# water-sensor.net
KiCad netlist of a schematic drawn in EAGLE
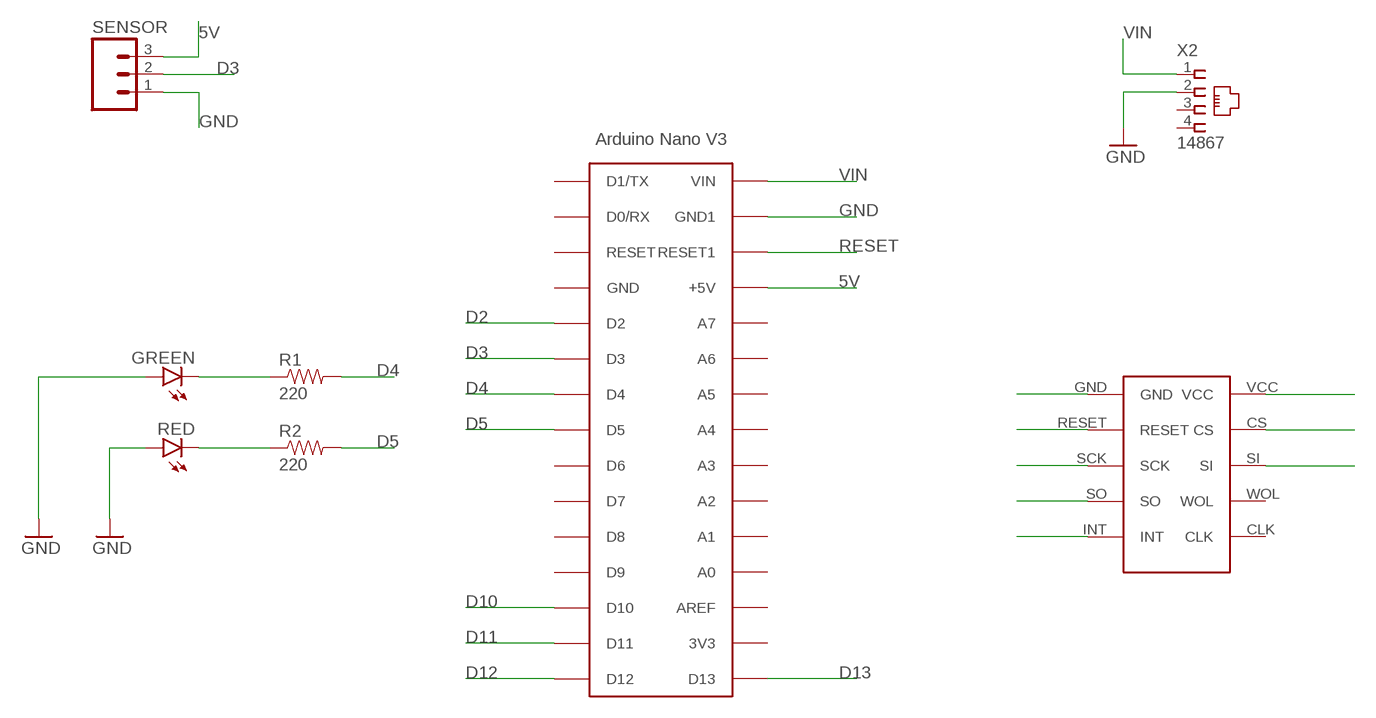
[diagram p0: schematic, sheet 1]

(export (version "E")
  (design (tool "Eeschema 10.0.6"))
  (components
    (comp (ref "GREEN")
      (value "LED3MM")
      (footprint "eagle-import:LED3MM")
      (libsource (lib "eagle-import") (part "LED3MM"))
    )
    (comp (ref "R1")
      (value "220")
      (footprint "eagle-import:AXIAL-0.5")
      (libsource (lib "eagle-import") (part "RESISTORPTH-1/2W"))
    )
    (comp (ref "R2")
      (value "220")
      (footprint "eagle-import:AXIAL-0.5")
      (libsource (lib "eagle-import") (part "RESISTORPTH-1/2W"))
    )
    (comp (ref "RED")
      (value "LED3MM")
      (footprint "eagle-import:LED3MM")
      (libsource (lib "eagle-import") (part "LED3MM"))
    )
    (comp (ref "SENSOR")
      (value "M03LONGPADS")
      (footprint "eagle-import:1X03_LONGPADS")
      (libsource (lib "eagle-import") (part "M03LONGPADS"))
    )
    (comp (ref "U$1")
      (value "ARDUINONANO")
      (footprint "eagle-import:PDIP-32")
      (libsource (lib "eagle-import") (part "ARDUINONANO"))
    )
    (comp (ref "U$2")
      (value "ENC28J60ENC28J60")
      (footprint "eagle-import:ENC28J60")
      (libsource (lib "eagle-import") (part "ENC28J60ENC28J60"))
    )
    (comp (ref "X2")
      (value "14867")
      (footprint "eagle-import:14867")
      (libsource (lib "eagle-import") (part "14867"))
    )
  )
  (nets
    (net (code "1") (name "/5V") (class "Default")
      (node (ref "SENSOR") (pin "3") (pinfunction "3_3") (pintype "passive"))
      (node (ref "U$1") (pin "+5V") (pinfunction "+5V_+5V") (pintype "bidirectional"))
      (node (ref "U$2") (pin "VCC") (pinfunction "VCC_VCC") (pintype "bidirectional"))
    )
    (net (code "2") (name "/D2") (class "Default")
      (node (ref "U$1") (pin "D2") (pinfunction "D2_D2") (pintype "bidirectional"))
      (node (ref "U$2") (pin "INT") (pinfunction "INT_INT") (pintype "bidirectional"))
    )
    (net (code "3") (name "/D3") (class "Default")
      (node (ref "SENSOR") (pin "2") (pinfunction "2_2") (pintype "passive"))
      (node (ref "U$1") (pin "D3") (pinfunction "D3_D3") (pintype "bidirectional"))
    )
    (net (code "4") (name "/D4") (class "Default")
      (node (ref "R1") (pin "P$2") (pinfunction "2_P$2") (pintype "passive"))
      (node (ref "U$1") (pin "D4") (pinfunction "D4_D4") (pintype "bidirectional"))
    )
    (net (code "5") (name "/D5") (class "Default")
      (node (ref "R2") (pin "P$2") (pinfunction "2_P$2") (pintype "passive"))
      (node (ref "U$1") (pin "D5") (pinfunction "D5_D5") (pintype "bidirectional"))
    )
    (net (code "6") (name "/D10") (class "Default")
      (node (ref "U$1") (pin "D10") (pinfunction "D10_D10") (pintype "bidirectional"))
      (node (ref "U$2") (pin "CS") (pinfunction "CS_CS") (pintype "bidirectional"))
    )
    (net (code "7") (name "/D11") (class "Default")
      (node (ref "U$1") (pin "D11") (pinfunction "D11_D11") (pintype "bidirectional"))
      (node (ref "U$2") (pin "SI") (pinfunction "SI_SI") (pintype "bidirectional"))
    )
    (net (code "8") (name "/D12") (class "Default")
      (node (ref "U$1") (pin "D12") (pinfunction "D12_D12") (pintype "bidirectional"))
      (node (ref "U$2") (pin "SO") (pinfunction "SO_SO") (pintype "bidirectional"))
    )
    (net (code "9") (name "/D13") (class "Default")
      (node (ref "U$1") (pin "D13") (pinfunction "D13_D13") (pintype "bidirectional"))
      (node (ref "U$2") (pin "SCK") (pinfunction "SCK_SCK") (pintype "bidirectional"))
    )
    (net (code "10") (name "/RESET") (class "Default")
      (node (ref "U$1") (pin "RESET1") (pinfunction "RESET1_RESET1") (pintype "bidirectional"))
      (node (ref "U$2") (pin "RESET") (pinfunction "RESET_RESET") (pintype "bidirectional"))
    )
    (net (code "11") (name "/VIN") (class "Default")
      (node (ref "U$1") (pin "VIN") (pinfunction "VIN_VIN") (pintype "bidirectional"))
      (node (ref "X2") (pin "1") (pinfunction "1_1") (pintype "passive"))
    )
    (net (code "12") (name "GND") (class "Default")
      (node (ref "GREEN") (pin "A") (pinfunction "A_A") (pintype "passive"))
      (node (ref "RED") (pin "A") (pinfunction "A_A") (pintype "passive"))
      (node (ref "SENSOR") (pin "1") (pinfunction "1_1") (pintype "passive"))
      (node (ref "U$1") (pin "GND1") (pinfunction "GND1_GND1") (pintype "bidirectional"))
      (node (ref "U$2") (pin "GND") (pinfunction "GND_GND") (pintype "bidirectional"))
      (node (ref "X2") (pin "2") (pinfunction "2_2") (pintype "passive"))
    )
    (net (code "13") (name "Net-(GREEN-C)") (class "Default")
      (node (ref "GREEN") (pin "K") (pinfunction "C_K") (pintype "passive"))
      (node (ref "R1") (pin "P$1") (pinfunction "1_P$1") (pintype "passive"))
    )
    (net (code "14") (name "Net-(R2-1)") (class "Default")
      (node (ref "R2") (pin "P$1") (pinfunction "1_P$1") (pintype "passive"))
      (node (ref "RED") (pin "K") (pinfunction "C_K") (pintype "passive"))
    )
    (net (code "15") (name "unconnected-(U$1-A0-PadA7)") (class "Default")
      (node (ref "U$1") (pin "A7") (pinfunction "A0_A7") (pintype "bidirectional"))
    )
    (net (code "16") (name "unconnected-(U$1-A1-PadA6)") (class "Default")
      (node (ref "U$1") (pin "A6") (pinfunction "A1_A6") (pintype "bidirectional"))
    )
    (net (code "17") (name "unconnected-(U$1-A2-PadA5)") (class "Default")
      (node (ref "U$1") (pin "A5") (pinfunction "A2_A5") (pintype "bidirectional"))
    )
    (net (code "18") (name "unconnected-(U$1-A3-PadA4)") (class "Default")
      (node (ref "U$1") (pin "A4") (pinfunction "A3_A4") (pintype "bidirectional"))
    )
    (net (code "19") (name "unconnected-(U$1-A4-PadA3)") (class "Default")
      (node (ref "U$1") (pin "A3") (pinfunction "A4_A3") (pintype "bidirectional"))
    )
    (net (code "20") (name "unconnected-(U$1-A5-PadA2)") (class "Default")
      (node (ref "U$1") (pin "A2") (pinfunction "A5_A2") (pintype "bidirectional"))
    )
    (net (code "21") (name "unconnected-(U$1-A6-PadA1)") (class "Default")
      (node (ref "U$1") (pin "A1") (pinfunction "A6_A1") (pintype "bidirectional"))
    )
    (net (code "22") (name "unconnected-(U$1-A7-PadA0)") (class "Default")
      (node (ref "U$1") (pin "A0") (pinfunction "A7_A0") (pintype "bidirectional"))
    )
    (net (code "23") (name "unconnected-(U$1-Pad3V3)") (class "Default")
      (node (ref "U$1") (pin "3V3") (pinfunction "3V3_3V3") (pintype "bidirectional"))
    )
    (net (code "24") (name "unconnected-(U$1-PadAREF)") (class "Default")
      (node (ref "U$1") (pin "AREF") (pinfunction "AREF_AREF") (pintype "bidirectional"))
    )
    (net (code "25") (name "unconnected-(U$1-PadD0{slash}RX)") (class "Default")
      (node (ref "U$1") (pin "D0/RX") (pinfunction "D0/RX_D0/RX") (pintype "bidirectional"))
    )
    (net (code "26") (name "unconnected-(U$1-PadD1{slash}TX)") (class "Default")
      (node (ref "U$1") (pin "D1/TX") (pinfunction "D1/TX_D1/TX") (pintype "bidirectional"))
    )
    (net (code "27") (name "unconnected-(U$1-PadD6)") (class "Default")
      (node (ref "U$1") (pin "D6") (pinfunction "D6_D6") (pintype "bidirectional"))
    )
    (net (code "28") (name "unconnected-(U$1-PadD7)") (class "Default")
      (node (ref "U$1") (pin "D7") (pinfunction "D7_D7") (pintype "bidirectional"))
    )
    (net (code "29") (name "unconnected-(U$1-PadD8)") (class "Default")
      (node (ref "U$1") (pin "D8") (pinfunction "D8_D8") (pintype "bidirectional"))
    )
    (net (code "30") (name "unconnected-(U$1-PadD9)") (class "Default")
      (node (ref "U$1") (pin "D9") (pinfunction "D9_D9") (pintype "bidirectional"))
    )
    (net (code "31") (name "unconnected-(U$1-PadGND)") (class "Default")
      (node (ref "U$1") (pin "GND") (pinfunction "GND_GND") (pintype "bidirectional"))
    )
    (net (code "32") (name "unconnected-(U$1-PadRESET)") (class "Default")
      (node (ref "U$1") (pin "RESET") (pinfunction "RESET_RESET") (pintype "bidirectional"))
    )
    (net (code "33") (name "unconnected-(U$2-PadCLK)") (class "Default")
      (node (ref "U$2") (pin "CLK") (pinfunction "CLK_CLK") (pintype "bidirectional"))
    )
    (net (code "34") (name "unconnected-(U$2-PadWOL)") (class "Default")
      (node (ref "U$2") (pin "WOL") (pinfunction "WOL_WOL") (pintype "bidirectional"))
    )
    (net (code "35") (name "unconnected-(X2-Pad3)") (class "Default")
      (node (ref "X2") (pin "3") (pinfunction "3_3") (pintype "passive"))
    )
    (net (code "36") (name "unconnected-(X2-Pad4)") (class "Default")
      (node (ref "X2") (pin "4") (pinfunction "4_4") (pintype "passive"))
    )
  )
)
